# OptoD.net
KiCad netlist of a schematic drawn in Altium Designer
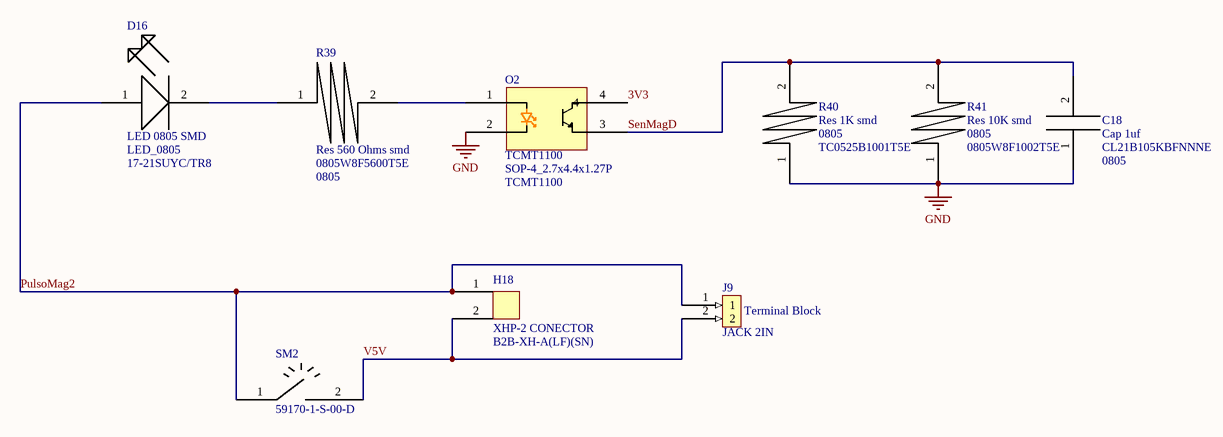
[diagram p0: OptoD.SchDoc]

(export (version "E")
  (design (tool "Eeschema 10.0.6"))
  (components
    (comp (ref "C18")
      (value "Cap 1uf")
      (footprint "CAP 1UFSMD")
      (fields (field (name "MFR.PART #") "CL21B105KBFNNNE") (field (name "PACKAGE") "0805"))
      (libsource (lib "Integrated_Library") (part "Cap 1uf"))
    )
    (comp (ref "D16")
      (value "LED 0805 SMD")
      (footprint "LED SMD Amarillo")
      (description "LED 0805 Yellow")
      (fields (field (name "PACKAGE") "LED_0805") (field (name "MFR.PART #") "17-21SUYC/TR8"))
      (libsource (lib "Integrated_Library") (part "LED 0805 SMD"))
    )
    (comp (ref "H18")
      (value "XHP-2 CONECTOR")
      (footprint "CONECTOR 2 PINES")
      (description "CONECTOR JST-XH 2 PINES")
      (fields (field (name "SUPPLIER NUMBER PART") "B2B-XH-A(LF)(SN)"))
      (libsource (lib "Practica 1") (part "B2B-XH-A(LF)(SN)"))
    )
    (comp (ref "J9")
      (value "JACK 2IN")
      (footprint "Terminal Blocks 2in")
      (description "Pluggable Terminal Blocks WR-TBL Mod312 5.08mm 2Pin Opn Hztl PCBHdr")
      (fields
        (field (name "MANUFACTURER") "Wurth Electronics")
        (field (name "MANUFACTURER PART NUMBER") "691312510002")
      )
      (libsource (lib "seguintII") (part "JACK 2IN"))
    )
    (comp (ref "O2")
      (value "TCMT1100")
      (footprint "TCMT110")
      (fields (field (name "PACKAGE") "SOP-4_2.7x4.4x1.27P") (field (name "MFR.PART #") "TCMT1100"))
      (libsource (lib "Integrated_Library") (part "TCMT110"))
    )
    (comp (ref "R39")
      (value "Res 560 Ohms smd")
      (footprint "RES 560")
      (description "Res 560 ohms smd")
      (fields (field (name "MFR.PART #") "0805W8F5600T5E") (field (name "PACKAGE") "0805"))
      (libsource (lib "Integrated_Library") (part "Res 560 Ohms smd"))
    )
    (comp (ref "R40")
      (value "Res 1K smd")
      (footprint "RES 1K")
      (fields (field (name "PACKAGE") "0805") (field (name "MFR.PART #") "TC0525B1001T5E"))
      (libsource (lib "Integrated_Library") (part "Res 1K smd"))
    )
    (comp (ref "R41")
      (value "Res 10K smd")
      (footprint "RES 10K")
      (description "10K")
      (fields (field (name "PACKAGE") "0805") (field (name "MFR.PART #") "0805W8F1002T5E"))
      (libsource (lib "Integrated_Library") (part "Res 10K smd"))
    )
    (comp (ref "SM2")
      (value "59170-1-S-00-D")
      (footprint "Switch Magnetico")
      (libsource (lib "Integrated_Library") (part "59170-1-S-00-D"))
    )
  )
  (nets
    (net (code "1") (name "/3V3") (class "Default")
      (node (ref "O2") (pin "4") (pinfunction "4_4") (pintype "passive"))
    )
    (net (code "2") (name "/PulsoMag2") (class "Default")
      (node (ref "D16") (pin "1") (pinfunction "1_1") (pintype "passive"))
      (node (ref "H18") (pin "1") (pinfunction "1_1") (pintype "passive"))
      (node (ref "J9") (pin "1") (pinfunction "1_1") (pintype "input"))
      (node (ref "SM2") (pin "1") (pinfunction "1_1") (pintype "passive"))
    )
    (net (code "3") (name "/SenMagD") (class "Default")
      (node (ref "C18") (pin "2") (pinfunction "2_2") (pintype "passive"))
      (node (ref "O2") (pin "3") (pinfunction "3_3") (pintype "passive"))
      (node (ref "R40") (pin "2") (pinfunction "2_2") (pintype "passive"))
      (node (ref "R41") (pin "2") (pinfunction "2_2") (pintype "passive"))
    )
    (net (code "4") (name "/V5V") (class "Default")
      (node (ref "H18") (pin "2") (pinfunction "2_2") (pintype "passive"))
      (node (ref "J9") (pin "2") (pinfunction "2_2") (pintype "input"))
      (node (ref "SM2") (pin "2") (pinfunction "2_2") (pintype "passive"))
    )
    (net (code "5") (name "GND") (class "Default")
      (node (ref "C18") (pin "1") (pinfunction "1_1") (pintype "passive"))
      (node (ref "O2") (pin "2") (pinfunction "2_2") (pintype "passive"))
      (node (ref "R40") (pin "1") (pinfunction "1_1") (pintype "passive"))
      (node (ref "R41") (pin "1") (pinfunction "1_1") (pintype "passive"))
    )
    (net (code "6") (name "Net-(D16-Pad2)") (class "Default")
      (node (ref "D16") (pin "2") (pinfunction "2_2") (pintype "passive"))
      (node (ref "R39") (pin "1") (pinfunction "1_1") (pintype "passive"))
    )
    (net (code "7") (name "Net-(O2-Pad1)") (class "Default")
      (node (ref "O2") (pin "1") (pinfunction "1_1") (pintype "passive"))
      (node (ref "R39") (pin "2") (pinfunction "2_2") (pintype "passive"))
    )
  )
)
